# avr-remocon.net
KiCad netlist of a schematic drawn in EAGLE
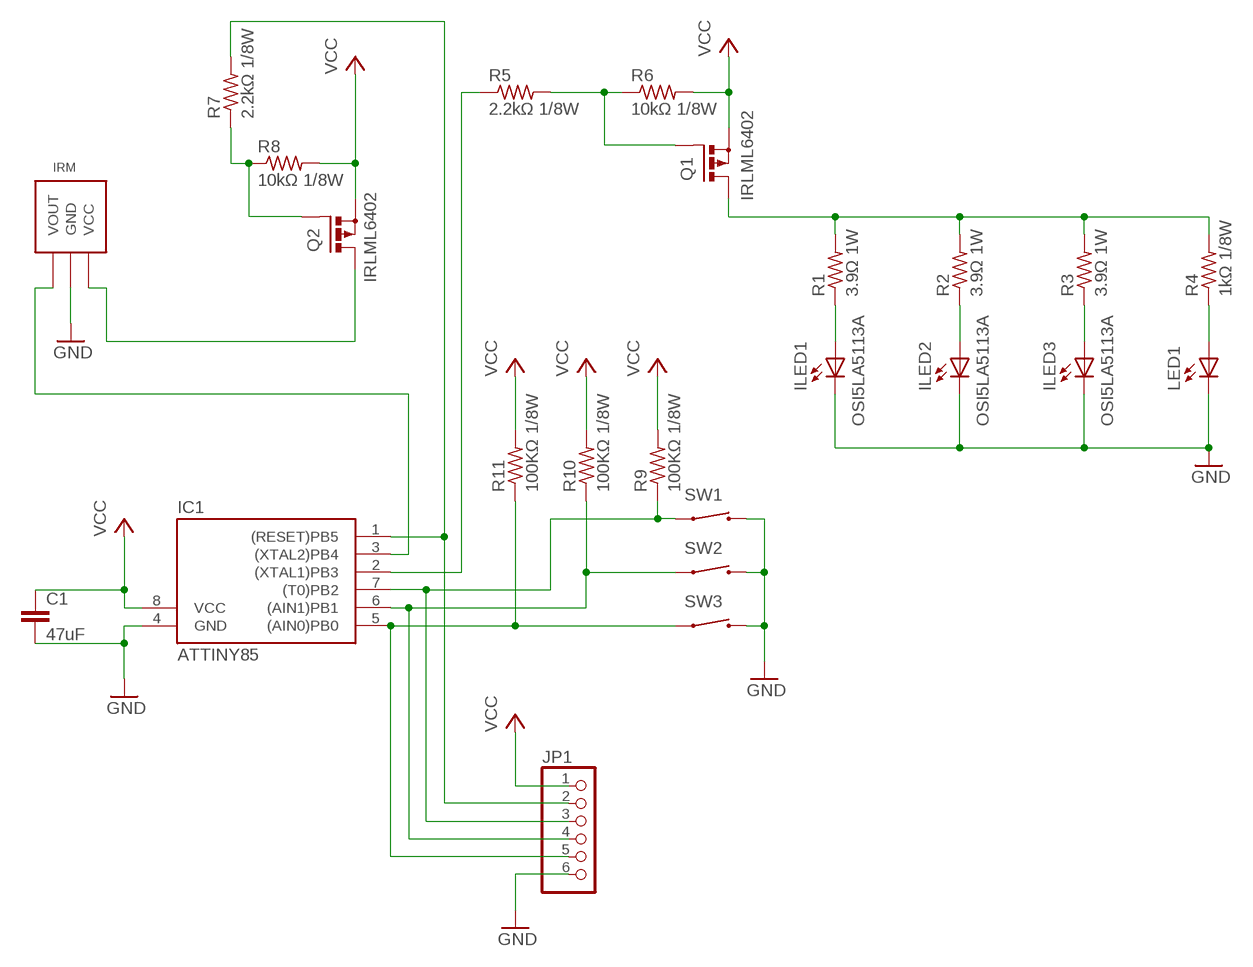
[diagram p0: schematic, sheet 1]

(export (version "E")
  (design (tool "Eeschema 10.0.6"))
  (components
    (comp (ref "C1")
      (value "47uF")
      (footprint "eagle-import:C3216")
      (libsource (lib "eagle-import") (part "C-EUC3216"))
    )
    (comp (ref "IC1")
      (value "ATTINY85")
      (footprint "eagle-import:SOIC8")
      (libsource (lib "eagle-import") (part "TINY10S"))
    )
    (comp (ref "ILED1")
      (value "OSI5LA5113A")
      (footprint "eagle-import:LED5MM-SIDE-DOWN3")
      (libsource (lib "eagle-import") (part "LED-SIDEDOWN3"))
    )
    (comp (ref "ILED2")
      (value "OSI5LA5113A")
      (footprint "eagle-import:LED5MM-SIDE-DOWN3")
      (libsource (lib "eagle-import") (part "LED-SIDEDOWN3"))
    )
    (comp (ref "ILED3")
      (value "OSI5LA5113A")
      (footprint "eagle-import:LED5MM-SIDE-DOWN3")
      (libsource (lib "eagle-import") (part "LED-SIDEDOWN3"))
    )
    (comp (ref "IRM")
      (value "IRM2161")
      (footprint "eagle-import:IRM2161")
      (libsource (lib "eagle-import") (part "IRM2161"))
    )
    (comp (ref "JP1")
      (value "PINHD-1X6")
      (footprint "eagle-import:1X06")
      (libsource (lib "eagle-import") (part "PINHD-1X6"))
    )
    (comp (ref "LED1")
      (value "LG_T679-E1F1-1")
      (footprint "eagle-import:PLCC2")
      (libsource (lib "eagle-import") (part "_T679-?-1E1F1LG"))
    )
    (comp (ref "Q1")
      (value "IRLML6402")
      (footprint "eagle-import:SOT-23")
      (libsource (lib "eagle-import") (part "IRLML6402"))
    )
    (comp (ref "Q2")
      (value "IRLML6402")
      (footprint "eagle-import:SOT-23")
      (libsource (lib "eagle-import") (part "IRLML6402"))
    )
    (comp (ref "R1")
      (value "3.9Ω 1W")
      (footprint "eagle-import:R2512W")
      (libsource (lib "eagle-import") (part "rcl_334_R-US_R2512W"))
    )
    (comp (ref "R2")
      (value "3.9Ω 1W")
      (footprint "eagle-import:R2512W")
      (libsource (lib "eagle-import") (part "rcl_334_R-US_R2512W"))
    )
    (comp (ref "R3")
      (value "3.9Ω 1W")
      (footprint "eagle-import:R2512W")
      (libsource (lib "eagle-import") (part "R-US_R2512W"))
    )
    (comp (ref "R4")
      (value "1kΩ 1/8W")
      (footprint "eagle-import:R0805")
      (libsource (lib "eagle-import") (part "R-US_R0805"))
    )
    (comp (ref "R5")
      (value "2.2kΩ 1/8W")
      (footprint "eagle-import:R0805")
      (libsource (lib "eagle-import") (part "R-US_R0805"))
    )
    (comp (ref "R6")
      (value "10kΩ 1/8W")
      (footprint "eagle-import:R0805")
      (libsource (lib "eagle-import") (part "R-US_R0805"))
    )
    (comp (ref "R7")
      (value "2.2kΩ 1/8W")
      (footprint "eagle-import:R0805")
      (libsource (lib "eagle-import") (part "rcl_334_R-US_R0805"))
    )
    (comp (ref "R8")
      (value "10kΩ 1/8W")
      (footprint "eagle-import:R0805")
      (libsource (lib "eagle-import") (part "rcl_334_R-US_R0805"))
    )
    (comp (ref "R9")
      (value "100KΩ 1/8W")
      (footprint "eagle-import:R0805")
      (libsource (lib "eagle-import") (part "R-US_R0805"))
    )
    (comp (ref "R10")
      (value "100KΩ 1/8W")
      (footprint "eagle-import:R0805")
      (libsource (lib "eagle-import") (part "R-US_R0805"))
    )
    (comp (ref "R11")
      (value "100KΩ 1/8W")
      (footprint "eagle-import:R0805")
      (libsource (lib "eagle-import") (part "R-US_R0805"))
    )
    (comp (ref "SW1")
      (value "RUBBER-SWITCH")
      (footprint "eagle-import:HALF-PITCH")
      (libsource (lib "eagle-import") (part "RUBBER-SWITCH"))
    )
    (comp (ref "SW2")
      (value "RUBBER-SWITCH")
      (footprint "eagle-import:HALF-PITCH")
      (libsource (lib "eagle-import") (part "RUBBER-SWITCH"))
    )
    (comp (ref "SW3")
      (value "RUBBER-SWITCH")
      (footprint "eagle-import:HALF-PITCH")
      (libsource (lib "eagle-import") (part "RUBBER-SWITCH"))
    )
  )
  (nets
    (net (code "1") (name "GND") (class "Default")
      (node (ref "C1") (pin "2") (pinfunction "2_2") (pintype "passive"))
      (node (ref "IC1") (pin "4") (pinfunction "GND_4") (pintype "power_in"))
      (node (ref "ILED1") (pin "K") (pinfunction "C_K") (pintype "passive"))
      (node (ref "ILED2") (pin "K") (pinfunction "C_K") (pintype "passive"))
      (node (ref "ILED3") (pin "K") (pinfunction "C_K") (pintype "passive"))
      (node (ref "IRM") (pin "P$2") (pinfunction "GND_P$2") (pintype "power_in"))
      (node (ref "JP1") (pin "6") (pinfunction "6_6") (pintype "passive"))
      (node (ref "LED1") (pin "C") (pinfunction "C_C") (pintype "passive"))
      (node (ref "SW1") (pin "P2") (pinfunction "2_P2") (pintype "passive"))
      (node (ref "SW2") (pin "P2") (pinfunction "2_P2") (pintype "passive"))
      (node (ref "SW3") (pin "P2") (pinfunction "2_P2") (pintype "passive"))
    )
    (net (code "2") (name "Net-(IC1-(AIN0)PB0)") (class "Default")
      (node (ref "IC1") (pin "5") (pinfunction "(AIN0)PB0_5") (pintype "bidirectional"))
      (node (ref "JP1") (pin "5") (pinfunction "5_5") (pintype "passive"))
      (node (ref "R11") (pin "1") (pinfunction "1_1") (pintype "passive"))
      (node (ref "SW3") (pin "P1") (pinfunction "1_P1") (pintype "passive"))
    )
    (net (code "3") (name "Net-(IC1-(AIN1)PB1)") (class "Default")
      (node (ref "IC1") (pin "6") (pinfunction "(AIN1)PB1_6") (pintype "bidirectional"))
      (node (ref "JP1") (pin "4") (pinfunction "4_4") (pintype "passive"))
      (node (ref "R10") (pin "1") (pinfunction "1_1") (pintype "passive"))
      (node (ref "SW2") (pin "P1") (pinfunction "1_P1") (pintype "passive"))
    )
    (net (code "4") (name "Net-(IC1-(RESET)PB5)") (class "Default")
      (node (ref "IC1") (pin "1") (pinfunction "(RESET)PB5_1") (pintype "bidirectional"))
      (node (ref "JP1") (pin "2") (pinfunction "2_2") (pintype "passive"))
      (node (ref "R7") (pin "2") (pinfunction "2_2") (pintype "passive"))
    )
    (net (code "5") (name "Net-(IC1-(T0)PB2)") (class "Default")
      (node (ref "IC1") (pin "7") (pinfunction "(T0)PB2_7") (pintype "bidirectional"))
      (node (ref "JP1") (pin "3") (pinfunction "3_3") (pintype "passive"))
      (node (ref "R9") (pin "1") (pinfunction "1_1") (pintype "passive"))
      (node (ref "SW1") (pin "P1") (pinfunction "1_P1") (pintype "passive"))
    )
    (net (code "6") (name "Net-(IC1-(XTAL1)PB3)") (class "Default")
      (node (ref "IC1") (pin "2") (pinfunction "(XTAL1)PB3_2") (pintype "bidirectional"))
      (node (ref "R5") (pin "1") (pinfunction "1_1") (pintype "passive"))
    )
    (net (code "7") (name "Net-(IC1-(XTAL2)PB4)") (class "Default")
      (node (ref "IC1") (pin "3") (pinfunction "(XTAL2)PB4_3") (pintype "bidirectional"))
      (node (ref "IRM") (pin "P$1") (pinfunction "VOUT_P$1") (pintype "bidirectional"))
    )
    (net (code "8") (name "Net-(ILED1-PadA)") (class "Default")
      (node (ref "ILED1") (pin "A") (pinfunction "A_A") (pintype "passive"))
      (node (ref "R1") (pin "1") (pinfunction "1_1") (pintype "passive"))
    )
    (net (code "9") (name "Net-(ILED2-PadA)") (class "Default")
      (node (ref "ILED2") (pin "A") (pinfunction "A_A") (pintype "passive"))
      (node (ref "R2") (pin "1") (pinfunction "1_1") (pintype "passive"))
    )
    (net (code "10") (name "Net-(ILED3-PadA)") (class "Default")
      (node (ref "ILED3") (pin "A") (pinfunction "A_A") (pintype "passive"))
      (node (ref "R3") (pin "1") (pinfunction "1_1") (pintype "passive"))
    )
    (net (code "11") (name "Net-(IRM-VCC)") (class "Default")
      (node (ref "IRM") (pin "P$3") (pinfunction "VCC_P$3") (pintype "power_in"))
      (node (ref "Q2") (pin "P3") (pinfunction "D_P3") (pintype "passive"))
    )
    (net (code "12") (name "Net-(LED1-PadA)") (class "Default")
      (node (ref "LED1") (pin "A") (pinfunction "A_A") (pintype "passive"))
      (node (ref "R4") (pin "1") (pinfunction "1_1") (pintype "passive"))
    )
    (net (code "13") (name "Net-(Q1-D)") (class "Default")
      (node (ref "Q1") (pin "P3") (pinfunction "D_P3") (pintype "passive"))
      (node (ref "R1") (pin "2") (pinfunction "2_2") (pintype "passive"))
      (node (ref "R2") (pin "2") (pinfunction "2_2") (pintype "passive"))
      (node (ref "R3") (pin "2") (pinfunction "2_2") (pintype "passive"))
      (node (ref "R4") (pin "2") (pinfunction "2_2") (pintype "passive"))
    )
    (net (code "14") (name "Net-(Q1-G)") (class "Default")
      (node (ref "Q1") (pin "P1") (pinfunction "G_P1") (pintype "passive"))
      (node (ref "R5") (pin "2") (pinfunction "2_2") (pintype "passive"))
      (node (ref "R6") (pin "1") (pinfunction "1_1") (pintype "passive"))
    )
    (net (code "15") (name "Net-(Q2-G)") (class "Default")
      (node (ref "Q2") (pin "P1") (pinfunction "G_P1") (pintype "passive"))
      (node (ref "R7") (pin "1") (pinfunction "1_1") (pintype "passive"))
      (node (ref "R8") (pin "1") (pinfunction "1_1") (pintype "passive"))
    )
    (net (code "16") (name "VCC") (class "Default")
      (node (ref "C1") (pin "1") (pinfunction "1_1") (pintype "passive"))
      (node (ref "IC1") (pin "8") (pinfunction "VCC_8") (pintype "power_in"))
      (node (ref "JP1") (pin "1") (pinfunction "1_1") (pintype "passive"))
      (node (ref "Q1") (pin "P2") (pinfunction "S_P2") (pintype "passive"))
      (node (ref "Q2") (pin "P2") (pinfunction "S_P2") (pintype "passive"))
      (node (ref "R10") (pin "2") (pinfunction "2_2") (pintype "passive"))
      (node (ref "R11") (pin "2") (pinfunction "2_2") (pintype "passive"))
      (node (ref "R6") (pin "2") (pinfunction "2_2") (pintype "passive"))
      (node (ref "R8") (pin "2") (pinfunction "2_2") (pintype "passive"))
      (node (ref "R9") (pin "2") (pinfunction "2_2") (pintype "passive"))
    )
  )
)
